# master_jorge2.net
KiCad netlist of a schematic drawn in EAGLE
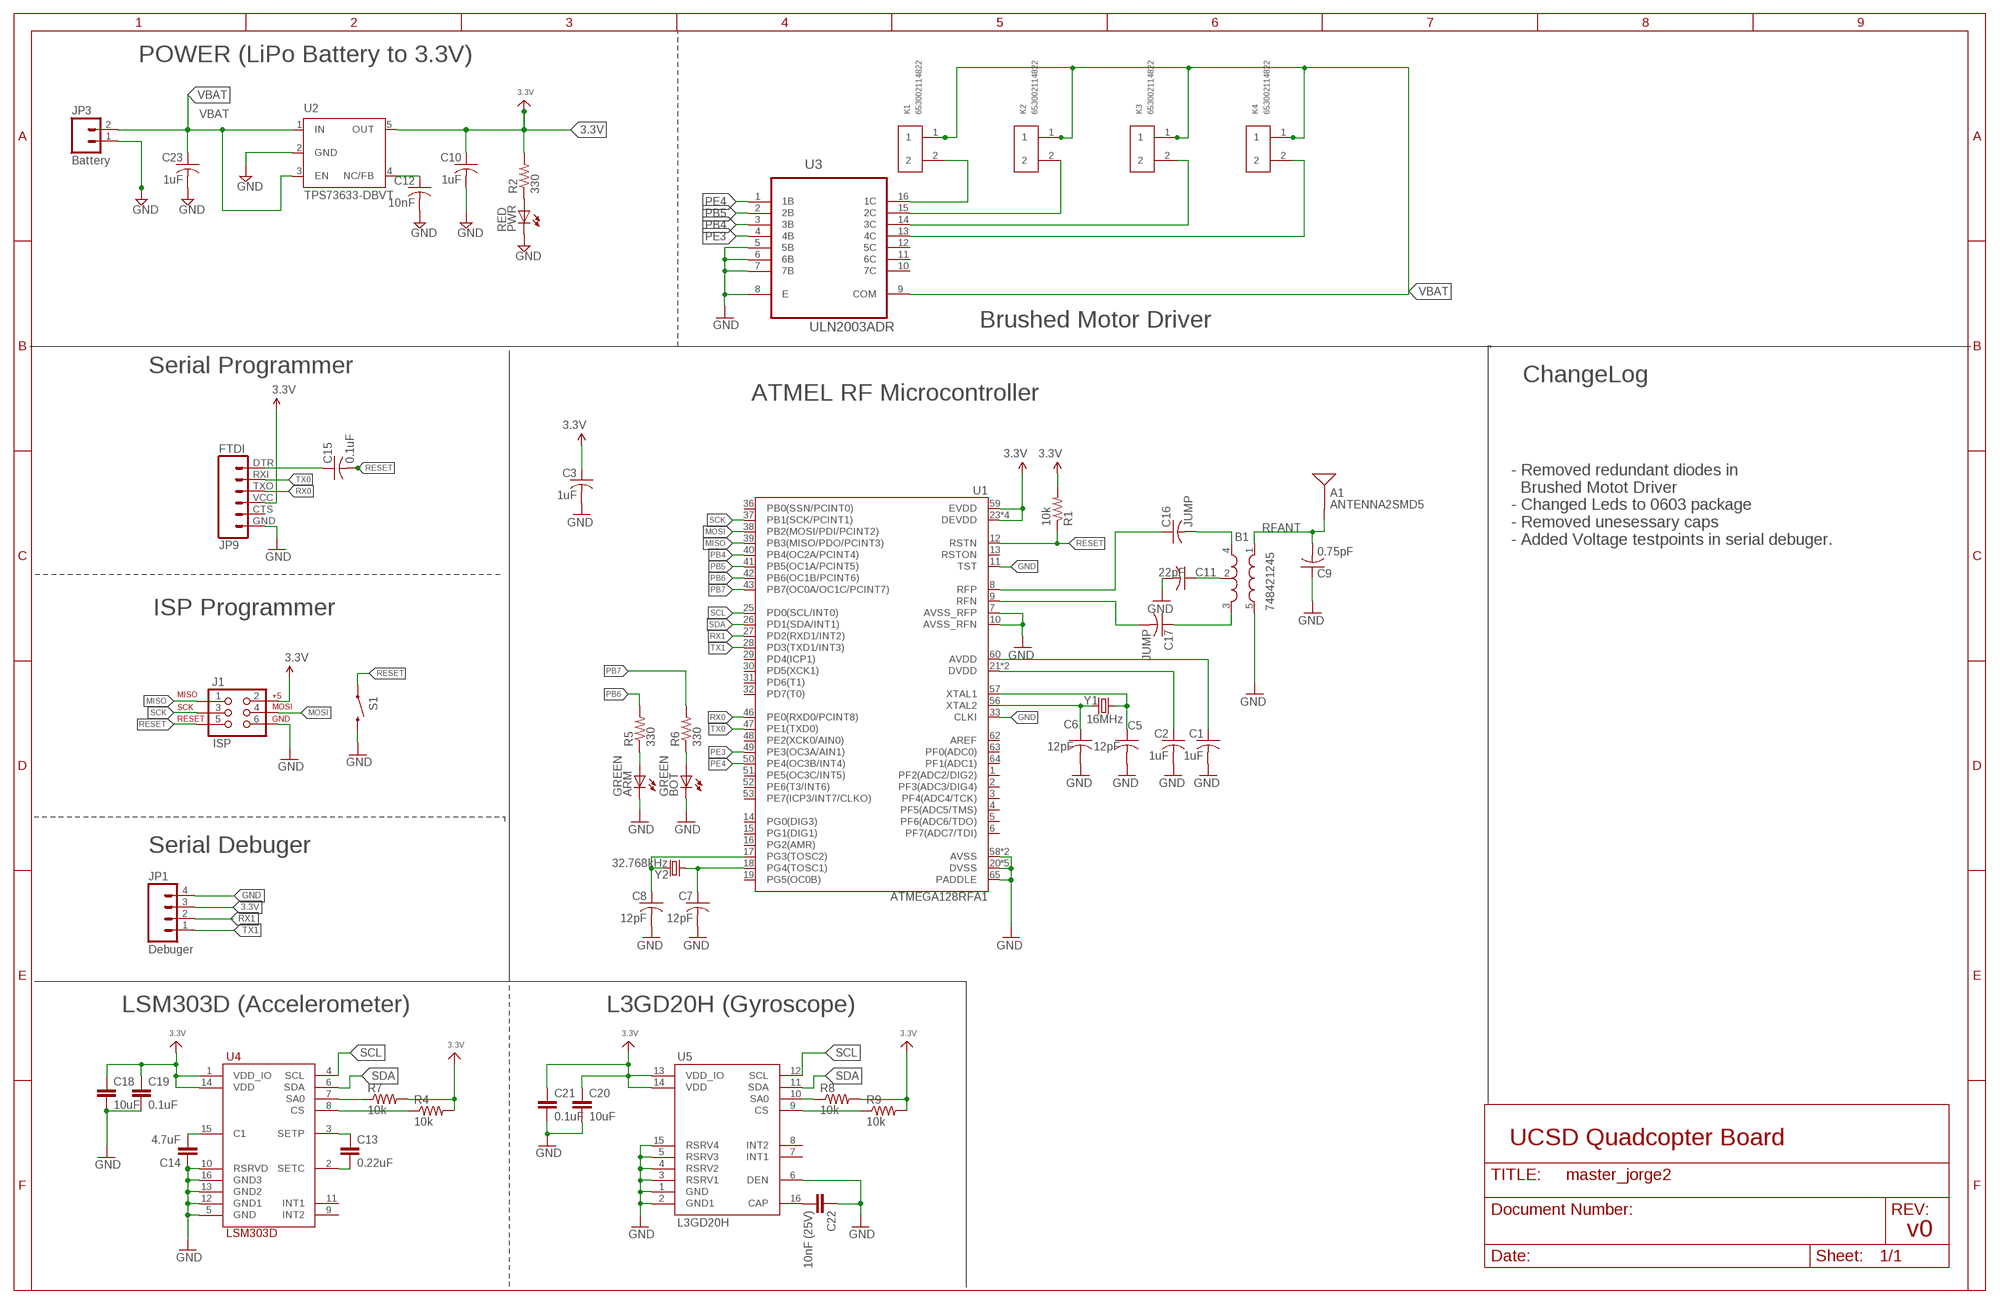
[diagram p0: schematic, sheet 1]

(export (version "E")
  (design (tool "Eeschema 10.0.6"))
  (components
    (comp (ref "A1")
      (value "ANTENNA2SMD5")
      (footprint "eagle-import:ANTENNA-CHIP5")
      (libsource (lib "eagle-import") (part "ANTENNA2SMD5"))
    )
    (comp (ref "ARM")
      (value "GREEN")
      (footprint "eagle-import:CHIPLED_0603")
      (libsource (lib "eagle-import") (part "LEDCHIPLED_0603"))
    )
    (comp (ref "B1")
      (value "748421245")
      (footprint "eagle-import:BALUN")
      (libsource (lib "eagle-import") (part "BALUN0805"))
    )
    (comp (ref "BOT")
      (value "GREEN")
      (footprint "eagle-import:CHIPLED_0603")
      (libsource (lib "eagle-import") (part "LEDCHIPLED_0603"))
    )
    (comp (ref "C1")
      (value "1uF")
      (footprint "eagle-import:C0805")
      (libsource (lib "eagle-import") (part "C-USC0805"))
    )
    (comp (ref "C2")
      (value "1uF")
      (footprint "eagle-import:C0805")
      (libsource (lib "eagle-import") (part "C-USC0805"))
    )
    (comp (ref "C3")
      (value "1uF")
      (footprint "eagle-import:C0805")
      (libsource (lib "eagle-import") (part "C-USC0805"))
    )
    (comp (ref "C5")
      (value "12pF")
      (footprint "eagle-import:C0805")
      (libsource (lib "eagle-import") (part "C-USC0805"))
    )
    (comp (ref "C6")
      (value "12pF")
      (footprint "eagle-import:C0805")
      (libsource (lib "eagle-import") (part "C-USC0805"))
    )
    (comp (ref "C7")
      (value "12pF")
      (footprint "eagle-import:C0805")
      (libsource (lib "eagle-import") (part "C-USC0805"))
    )
    (comp (ref "C8")
      (value "12pF")
      (footprint "eagle-import:C0805")
      (libsource (lib "eagle-import") (part "C-USC0805"))
    )
    (comp (ref "C9")
      (value "0.75pF")
      (footprint "eagle-import:C0805")
      (libsource (lib "eagle-import") (part "C-USC0805"))
    )
    (comp (ref "C10")
      (value "1uF")
      (footprint "eagle-import:C0805")
      (libsource (lib "eagle-import") (part "C-USC0805"))
    )
    (comp (ref "C11")
      (value "22pF")
      (footprint "eagle-import:C0805")
      (libsource (lib "eagle-import") (part "C-USC0805"))
    )
    (comp (ref "C12")
      (value "10nF")
      (footprint "eagle-import:C0805")
      (libsource (lib "eagle-import") (part "C-USC0805"))
    )
    (comp (ref "C13")
      (value "0.22uF")
      (footprint "eagle-import:0805")
      (libsource (lib "eagle-import") (part "CAP0805"))
    )
    (comp (ref "C14")
      (value "4.7uF")
      (footprint "eagle-import:0805")
      (libsource (lib "eagle-import") (part "CAP0805"))
    )
    (comp (ref "C15")
      (value "0.1uF")
      (footprint "eagle-import:C0805")
      (libsource (lib "eagle-import") (part "C-USC0805"))
    )
    (comp (ref "C16")
      (value "JUMP")
      (footprint "eagle-import:C0805")
      (libsource (lib "eagle-import") (part "C-USC0805"))
    )
    (comp (ref "C17")
      (value "JUMP")
      (footprint "eagle-import:C0805")
      (libsource (lib "eagle-import") (part "C-USC0805"))
    )
    (comp (ref "C18")
      (value "10uF")
      (footprint "eagle-import:0805")
      (libsource (lib "eagle-import") (part "CAP0805"))
    )
    (comp (ref "C19")
      (value "0.1uF")
      (footprint "eagle-import:0805")
      (libsource (lib "eagle-import") (part "CAP0805"))
    )
    (comp (ref "C20")
      (value "10uF")
      (footprint "eagle-import:0805")
      (libsource (lib "eagle-import") (part "CAP0805"))
    )
    (comp (ref "C21")
      (value "0.1uF")
      (footprint "eagle-import:0805")
      (libsource (lib "eagle-import") (part "CAP0805"))
    )
    (comp (ref "C22")
      (value "10nF (25V)")
      (footprint "eagle-import:0805")
      (libsource (lib "eagle-import") (part "CAP0805"))
    )
    (comp (ref "C23")
      (value "1uF")
      (footprint "eagle-import:C0805")
      (libsource (lib "eagle-import") (part "C-USC0805"))
    )
    (comp (ref "J1")
      (value "ISP")
      (footprint "eagle-import:2X3-NS")
      (libsource (lib "eagle-import") (part "AVR_SPI_PRG_6NS"))
    )
    (comp (ref "JP1")
      (value "Debuger")
      (footprint "eagle-import:1X04")
      (libsource (lib "eagle-import") (part "M04PTH"))
    )
    (comp (ref "JP3")
      (value "Battery")
      (footprint "eagle-import:1X02")
      (libsource (lib "eagle-import") (part "M02PTH"))
    )
    (comp (ref "JP9")
      (value "FTDI")
      (footprint "eagle-import:FTDI_BASIC")
      (libsource (lib "eagle-import") (part "FTDI_BASICPTH"))
    )
    (comp (ref "K1")
      (value "653002114822")
      (footprint "eagle-import:653002114822")
      (libsource (lib "eagle-import") (part "653002114822"))
    )
    (comp (ref "K2")
      (value "653002114822")
      (footprint "eagle-import:653002114822")
      (libsource (lib "eagle-import") (part "653002114822"))
    )
    (comp (ref "K3")
      (value "653002114822")
      (footprint "eagle-import:653002114822")
      (libsource (lib "eagle-import") (part "653002114822"))
    )
    (comp (ref "K4")
      (value "653002114822")
      (footprint "eagle-import:653002114822")
      (libsource (lib "eagle-import") (part "653002114822"))
    )
    (comp (ref "PWR")
      (value "RED")
      (footprint "eagle-import:CHIPLED_0603")
      (libsource (lib "eagle-import") (part "LEDCHIPLED_0603"))
    )
    (comp (ref "R1")
      (value "10k")
      (footprint "eagle-import:R0805")
      (libsource (lib "eagle-import") (part "R-US_R0805"))
    )
    (comp (ref "R2")
      (value "330")
      (footprint "eagle-import:R0805")
      (libsource (lib "eagle-import") (part "R-US_R0805"))
    )
    (comp (ref "R4")
      (value "10k")
      (footprint "eagle-import:0805")
      (libsource (lib "eagle-import") (part "RESISTOR0805-RES"))
    )
    (comp (ref "R5")
      (value "330")
      (footprint "eagle-import:R0805")
      (libsource (lib "eagle-import") (part "R-US_R0805"))
    )
    (comp (ref "R6")
      (value "330")
      (footprint "eagle-import:R0805")
      (libsource (lib "eagle-import") (part "R-US_R0805"))
    )
    (comp (ref "R7")
      (value "10k")
      (footprint "eagle-import:0805")
      (libsource (lib "eagle-import") (part "RESISTOR0805-RES"))
    )
    (comp (ref "R8")
      (value "10k")
      (footprint "eagle-import:0805")
      (libsource (lib "eagle-import") (part "RESISTOR0805-RES"))
    )
    (comp (ref "R9")
      (value "10k")
      (footprint "eagle-import:0805")
      (libsource (lib "eagle-import") (part "RESISTOR0805-RES"))
    )
    (comp (ref "S1")
      (value "SWITCH-MOMENTARY-2SMD")
      (footprint "eagle-import:TACTILE_SWITCH_SMD")
      (libsource (lib "eagle-import") (part "SWITCH-MOMENTARY-2SMD"))
    )
    (comp (ref "U1")
      (value "ATMEGA128RFA1")
      (footprint "eagle-import:QFN-64")
      (libsource (lib "eagle-import") (part "ATMEGA128RFA1"))
    )
    (comp (ref "U2")
      (value "TPS73633-DBVT")
      (footprint "eagle-import:SOT23-DBV")
      (libsource (lib "eagle-import") (part "TPS73633-DBVT"))
    )
    (comp (ref "U3")
      (value "ULN2003ADR")
      (footprint "eagle-import:SOIC127P600X175-16N")
      (libsource (lib "eagle-import") (part "ULN2003ADR"))
    )
    (comp (ref "U4")
      (value "LSM303D")
      (footprint "eagle-import:LGA16_3X3MM")
      (libsource (lib "eagle-import") (part "LSM303D"))
    )
    (comp (ref "U5")
      (value "L3GD20H")
      (footprint "eagle-import:LGA16_3X3MM")
      (libsource (lib "eagle-import") (part "L3GD20H"))
    )
    (comp (ref "Y1")
      (value "16MHz")
      (footprint "eagle-import:CRYSTAL-SMD-5X3")
      (libsource (lib "eagle-import") (part "CRYSTAL5X3"))
    )
    (comp (ref "Y2")
      (value "32.768kHz")
      (footprint "eagle-import:CRYSTAL-32KHZ-SMD")
      (libsource (lib "eagle-import") (part "CRYSTAL32-SMD"))
    )
  )
  (nets
    (net (code "1") (name "/RFANT") (class "Default")
      (node (ref "A1") (pin "FEED") (pinfunction "SIGNAL_FEED") (pintype "bidirectional"))
      (node (ref "B1") (pin "1") (pinfunction "IN_1") (pintype "bidirectional"))
      (node (ref "C9") (pin "2") (pinfunction "2_2") (pintype "passive"))
    )
    (net (code "2") (name "3.3V") (class "Default")
      (node (ref "C10") (pin "1") (pinfunction "1_1") (pintype "passive"))
      (node (ref "C18") (pin "1") (pinfunction "1_1") (pintype "passive"))
      (node (ref "C19") (pin "1") (pinfunction "1_1") (pintype "passive"))
      (node (ref "C20") (pin "1") (pinfunction "1_1") (pintype "passive"))
      (node (ref "C21") (pin "1") (pinfunction "1_1") (pintype "passive"))
      (node (ref "C3") (pin "1") (pinfunction "1_1") (pintype "passive"))
      (node (ref "J1") (pin "2") (pinfunction "2_2") (pintype "passive"))
      (node (ref "JP1") (pin "3") (pinfunction "3_3") (pintype "passive"))
      (node (ref "JP9") (pin "VCC") (pinfunction "4_VCC") (pintype "passive"))
      (node (ref "R1") (pin "2") (pinfunction "2_2") (pintype "passive"))
      (node (ref "R2") (pin "2") (pinfunction "2_2") (pintype "passive"))
      (node (ref "R4") (pin "2") (pinfunction "2_2") (pintype "passive"))
      (node (ref "R7") (pin "2") (pinfunction "2_2") (pintype "passive"))
      (node (ref "R8") (pin "2") (pinfunction "2_2") (pintype "passive"))
      (node (ref "R9") (pin "2") (pinfunction "2_2") (pintype "passive"))
      (node (ref "U1") (pin "23") (pinfunction "DEVDD_23") (pintype "bidirectional"))
      (node (ref "U1") (pin "34") (pinfunction "DEVDD_34") (pintype "bidirectional"))
      (node (ref "U1") (pin "44") (pinfunction "DEVDD_44") (pintype "bidirectional"))
      (node (ref "U1") (pin "54") (pinfunction "DEVDD_54") (pintype "bidirectional"))
      (node (ref "U1") (pin "59") (pinfunction "EVDD_59") (pintype "bidirectional"))
      (node (ref "U2") (pin "5") (pinfunction "OUT_5") (pintype "passive"))
      (node (ref "U4") (pin "1") (pinfunction "VDD_IO_1") (pintype "bidirectional"))
      (node (ref "U4") (pin "14") (pinfunction "VDD_14") (pintype "bidirectional"))
      (node (ref "U5") (pin "13") (pinfunction "VDD_IO_13") (pintype "bidirectional"))
      (node (ref "U5") (pin "14") (pinfunction "VDD_14") (pintype "bidirectional"))
    )
    (net (code "3") (name "GND") (class "Default")
      (node (ref "ARM") (pin "C") (pinfunction "C_C") (pintype "passive"))
      (node (ref "B1") (pin "5") (pinfunction "GND_5") (pintype "bidirectional"))
      (node (ref "BOT") (pin "C") (pinfunction "C_C") (pintype "passive"))
      (node (ref "C1") (pin "2") (pinfunction "2_2") (pintype "passive"))
      (node (ref "C10") (pin "2") (pinfunction "2_2") (pintype "passive"))
      (node (ref "C11") (pin "2") (pinfunction "2_2") (pintype "passive"))
      (node (ref "C12") (pin "2") (pinfunction "2_2") (pintype "passive"))
      (node (ref "C14") (pin "1") (pinfunction "1_1") (pintype "passive"))
      (node (ref "C18") (pin "2") (pinfunction "2_2") (pintype "passive"))
      (node (ref "C19") (pin "2") (pinfunction "2_2") (pintype "passive"))
      (node (ref "C2") (pin "2") (pinfunction "2_2") (pintype "passive"))
      (node (ref "C20") (pin "2") (pinfunction "2_2") (pintype "passive"))
      (node (ref "C21") (pin "2") (pinfunction "2_2") (pintype "passive"))
      (node (ref "C22") (pin "1") (pinfunction "1_1") (pintype "passive"))
      (node (ref "C23") (pin "2") (pinfunction "2_2") (pintype "passive"))
      (node (ref "C3") (pin "2") (pinfunction "2_2") (pintype "passive"))
      (node (ref "C5") (pin "2") (pinfunction "2_2") (pintype "passive"))
      (node (ref "C6") (pin "2") (pinfunction "2_2") (pintype "passive"))
      (node (ref "C7") (pin "2") (pinfunction "2_2") (pintype "passive"))
      (node (ref "C8") (pin "2") (pinfunction "2_2") (pintype "passive"))
      (node (ref "C9") (pin "1") (pinfunction "1_1") (pintype "passive"))
      (node (ref "J1") (pin "6") (pinfunction "6_6") (pintype "passive"))
      (node (ref "JP1") (pin "4") (pinfunction "4_4") (pintype "passive"))
      (node (ref "JP3") (pin "1") (pinfunction "1_1") (pintype "passive"))
      (node (ref "JP9") (pin "GND") (pinfunction "6_GND") (pintype "passive"))
      (node (ref "PWR") (pin "C") (pinfunction "C_C") (pintype "passive"))
      (node (ref "S1") (pin "3") (pinfunction "2_3") (pintype "passive"))
      (node (ref "U1") (pin "10") (pinfunction "AVSS_RFN_10") (pintype "bidirectional"))
      (node (ref "U1") (pin "11") (pinfunction "TST_11") (pintype "bidirectional"))
      (node (ref "U1") (pin "20") (pinfunction "DVSS_20") (pintype "bidirectional"))
      (node (ref "U1") (pin "24") (pinfunction "DVSS_24") (pintype "bidirectional"))
      (node (ref "U1") (pin "33") (pinfunction "CLKI_33") (pintype "bidirectional"))
      (node (ref "U1") (pin "35") (pinfunction "DVSS_35") (pintype "bidirectional"))
      (node (ref "U1") (pin "45") (pinfunction "DVSS_45") (pintype "bidirectional"))
      (node (ref "U1") (pin "55") (pinfunction "DVSS_55") (pintype "bidirectional"))
      (node (ref "U1") (pin "58") (pinfunction "AVSS_58") (pintype "bidirectional"))
      (node (ref "U1") (pin "61") (pinfunction "AVSS_61") (pintype "bidirectional"))
      (node (ref "U1") (pin "65") (pinfunction "PADDLE_65") (pintype "bidirectional"))
      (node (ref "U1") (pin "7") (pinfunction "AVSS_RFP_7") (pintype "bidirectional"))
      (node (ref "U2") (pin "2") (pinfunction "GND_2") (pintype "input"))
      (node (ref "U3") (pin "5") (pinfunction "5B_5") (pintype "input"))
      (node (ref "U3") (pin "6") (pinfunction "6B_6") (pintype "input"))
      (node (ref "U3") (pin "7") (pinfunction "7B_7") (pintype "input"))
      (node (ref "U3") (pin "8") (pinfunction "E_8") (pintype "input"))
      (node (ref "U4") (pin "10") (pinfunction "RSRVD_10") (pintype "bidirectional"))
      (node (ref "U4") (pin "12") (pinfunction "GND1_12") (pintype "bidirectional"))
      (node (ref "U4") (pin "13") (pinfunction "GND2_13") (pintype "bidirectional"))
      (node (ref "U4") (pin "16") (pinfunction "GND3_16") (pintype "bidirectional"))
      (node (ref "U4") (pin "5") (pinfunction "GND_5") (pintype "bidirectional"))
      (node (ref "U5") (pin "1") (pinfunction "GND_1") (pintype "bidirectional"))
      (node (ref "U5") (pin "15") (pinfunction "RSRV4_15") (pintype "bidirectional"))
      (node (ref "U5") (pin "2") (pinfunction "GND1_2") (pintype "bidirectional"))
      (node (ref "U5") (pin "3") (pinfunction "RSRV1_3") (pintype "bidirectional"))
      (node (ref "U5") (pin "4") (pinfunction "RSRV2_4") (pintype "bidirectional"))
      (node (ref "U5") (pin "5") (pinfunction "RSRV3_5") (pintype "bidirectional"))
      (node (ref "U5") (pin "6") (pinfunction "DEN_6") (pintype "bidirectional"))
    )
    (net (code "4") (name "MISO") (class "Default")
      (node (ref "J1") (pin "1") (pinfunction "1_1") (pintype "passive"))
      (node (ref "U1") (pin "39") (pinfunction "PB3(MISO/PDO/PCINT3)_39") (pintype "bidirectional"))
    )
    (net (code "5") (name "MOSI") (class "Default")
      (node (ref "J1") (pin "4") (pinfunction "4_4") (pintype "passive"))
      (node (ref "U1") (pin "38") (pinfunction "PB2(MOSI/PDI/PCINT2)_38") (pintype "bidirectional"))
    )
    (net (code "6") (name "Net-(ARM-PadA)") (class "Default")
      (node (ref "ARM") (pin "A") (pinfunction "A_A") (pintype "passive"))
      (node (ref "R5") (pin "1") (pinfunction "1_1") (pintype "passive"))
    )
    (net (code "7") (name "Net-(B1-GND-Pad2)") (class "Default")
      (node (ref "B1") (pin "2") (pinfunction "GND_2") (pintype "bidirectional"))
      (node (ref "C11") (pin "1") (pinfunction "1_1") (pintype "passive"))
    )
    (net (code "8") (name "Net-(B1-OUT1)") (class "Default")
      (node (ref "B1") (pin "4") (pinfunction "OUT1_4") (pintype "bidirectional"))
      (node (ref "C16") (pin "2") (pinfunction "2_2") (pintype "passive"))
    )
    (net (code "9") (name "Net-(B1-OUT2)") (class "Default")
      (node (ref "B1") (pin "3") (pinfunction "OUT2_3") (pintype "bidirectional"))
      (node (ref "C17") (pin "1") (pinfunction "1_1") (pintype "passive"))
    )
    (net (code "10") (name "Net-(BOT-PadA)") (class "Default")
      (node (ref "BOT") (pin "A") (pinfunction "A_A") (pintype "passive"))
      (node (ref "R6") (pin "1") (pinfunction "1_1") (pintype "passive"))
    )
    (net (code "11") (name "Net-(C2-Pad1)") (class "Default")
      (node (ref "C2") (pin "1") (pinfunction "1_1") (pintype "passive"))
      (node (ref "U1") (pin "21") (pinfunction "DVDD_21") (pintype "bidirectional"))
      (node (ref "U1") (pin "22") (pinfunction "DVDD_22") (pintype "bidirectional"))
    )
    (net (code "12") (name "Net-(JP9-1)") (class "Default")
      (node (ref "C15") (pin "1") (pinfunction "1_1") (pintype "passive"))
      (node (ref "JP9") (pin "DTR") (pinfunction "1_DTR") (pintype "passive"))
    )
    (net (code "13") (name "Net-(PWR-PadA)") (class "Default")
      (node (ref "PWR") (pin "A") (pinfunction "A_A") (pintype "passive"))
      (node (ref "R2") (pin "1") (pinfunction "1_1") (pintype "passive"))
    )
    (net (code "14") (name "Net-(U1-AVDD)") (class "Default")
      (node (ref "C1") (pin "1") (pinfunction "1_1") (pintype "passive"))
      (node (ref "U1") (pin "60") (pinfunction "AVDD_60") (pintype "bidirectional"))
    )
    (net (code "15") (name "Net-(U1-PG3(TOSC2))") (class "Default")
      (node (ref "C8") (pin "1") (pinfunction "1_1") (pintype "passive"))
      (node (ref "U1") (pin "17") (pinfunction "PG3(TOSC2)_17") (pintype "bidirectional"))
      (node (ref "Y2") (pin "X2") (pinfunction "2_X2") (pintype "passive"))
    )
    (net (code "16") (name "Net-(U1-PG4(TOSC1))") (class "Default")
      (node (ref "C7") (pin "1") (pinfunction "1_1") (pintype "passive"))
      (node (ref "U1") (pin "18") (pinfunction "PG4(TOSC1)_18") (pintype "bidirectional"))
      (node (ref "Y2") (pin "X1") (pinfunction "1_X1") (pintype "passive"))
    )
    (net (code "17") (name "Net-(U1-RFN)") (class "Default")
      (node (ref "C17") (pin "2") (pinfunction "2_2") (pintype "passive"))
      (node (ref "U1") (pin "9") (pinfunction "RFN_9") (pintype "bidirectional"))
    )
    (net (code "18") (name "Net-(U1-RFP)") (class "Default")
      (node (ref "C16") (pin "1") (pinfunction "1_1") (pintype "passive"))
      (node (ref "U1") (pin "8") (pinfunction "RFP_8") (pintype "bidirectional"))
    )
    (net (code "19") (name "Net-(U1-XTAL1)") (class "Default")
      (node (ref "C5") (pin "1") (pinfunction "1_1") (pintype "passive"))
      (node (ref "U1") (pin "57") (pinfunction "XTAL1_57") (pintype "bidirectional"))
      (node (ref "Y1") (pin "3") (pinfunction "2_3") (pintype "passive"))
    )
    (net (code "20") (name "Net-(U1-XTAL2)") (class "Default")
      (node (ref "C6") (pin "1") (pinfunction "1_1") (pintype "passive"))
      (node (ref "U1") (pin "56") (pinfunction "XTAL2_56") (pintype "bidirectional"))
      (node (ref "Y1") (pin "1") (pinfunction "1_1") (pintype "passive"))
    )
    (net (code "21") (name "Net-(U2-NC{slash}FB)") (class "Default")
      (node (ref "C12") (pin "1") (pinfunction "1_1") (pintype "passive"))
      (node (ref "U2") (pin "4") (pinfunction "NC/FB_4") (pintype "passive"))
    )
    (net (code "22") (name "Net-(U3-1C)") (class "Default")
      (node (ref "K1") (pin "2") (pinfunction "2_2") (pintype "bidirectional"))
      (node (ref "U3") (pin "16") (pinfunction "1C_16") (pintype "output"))
    )
    (net (code "23") (name "Net-(U3-2C)") (class "Default")
      (node (ref "K2") (pin "2") (pinfunction "2_2") (pintype "bidirectional"))
      (node (ref "U3") (pin "15") (pinfunction "2C_15") (pintype "output"))
    )
    (net (code "24") (name "Net-(U3-3C)") (class "Default")
      (node (ref "K3") (pin "2") (pinfunction "2_2") (pintype "bidirectional"))
      (node (ref "U3") (pin "14") (pinfunction "3C_14") (pintype "output"))
    )
    (net (code "25") (name "Net-(U3-4C)") (class "Default")
      (node (ref "K4") (pin "2") (pinfunction "2_2") (pintype "bidirectional"))
      (node (ref "U3") (pin "13") (pinfunction "4C_13") (pintype "output"))
    )
    (net (code "26") (name "Net-(U4-C1)") (class "Default")
      (node (ref "C14") (pin "2") (pinfunction "2_2") (pintype "passive"))
      (node (ref "U4") (pin "15") (pinfunction "C1_15") (pintype "bidirectional"))
    )
    (net (code "27") (name "Net-(U4-CS)") (class "Default")
      (node (ref "R4") (pin "1") (pinfunction "1_1") (pintype "passive"))
      (node (ref "U4") (pin "8") (pinfunction "CS_8") (pintype "bidirectional"))
    )
    (net (code "28") (name "Net-(U4-SA0)") (class "Default")
      (node (ref "R7") (pin "1") (pinfunction "1_1") (pintype "passive"))
      (node (ref "U4") (pin "7") (pinfunction "SA0_7") (pintype "bidirectional"))
    )
    (net (code "29") (name "Net-(U4-SETC)") (class "Default")
      (node (ref "C13") (pin "2") (pinfunction "2_2") (pintype "passive"))
      (node (ref "U4") (pin "2") (pinfunction "SETC_2") (pintype "bidirectional"))
    )
    (net (code "30") (name "Net-(U4-SETP)") (class "Default")
      (node (ref "C13") (pin "1") (pinfunction "1_1") (pintype "passive"))
      (node (ref "U4") (pin "3") (pinfunction "SETP_3") (pintype "bidirectional"))
    )
    (net (code "31") (name "Net-(U5-CAP)") (class "Default")
      (node (ref "C22") (pin "2") (pinfunction "2_2") (pintype "passive"))
      (node (ref "U5") (pin "16") (pinfunction "CAP_16") (pintype "bidirectional"))
    )
    (net (code "32") (name "Net-(U5-CS)") (class "Default")
      (node (ref "R9") (pin "1") (pinfunction "1_1") (pintype "passive"))
      (node (ref "U5") (pin "9") (pinfunction "CS_9") (pintype "bidirectional"))
    )
    (net (code "33") (name "Net-(U5-SA0)") (class "Default")
      (node (ref "R8") (pin "1") (pinfunction "1_1") (pintype "passive"))
      (node (ref "U5") (pin "10") (pinfunction "SA0_10") (pintype "bidirectional"))
    )
    (net (code "34") (name "PB4") (class "Default")
      (node (ref "U1") (pin "40") (pinfunction "PB4(OC2A/PCINT4)_40") (pintype "bidirectional"))
      (node (ref "U3") (pin "3") (pinfunction "3B_3") (pintype "input"))
    )
    (net (code "35") (name "PB5") (class "Default")
      (node (ref "U1") (pin "41") (pinfunction "PB5(OC1A/PCINT5)_41") (pintype "bidirectional"))
      (node (ref "U3") (pin "2") (pinfunction "2B_2") (pintype "input"))
    )
    (net (code "36") (name "PB6") (class "Default")
      (node (ref "R5") (pin "2") (pinfunction "2_2") (pintype "passive"))
      (node (ref "U1") (pin "42") (pinfunction "PB6(OC1B/PCINT6)_42") (pintype "bidirectional"))
    )
    (net (code "37") (name "PB7") (class "Default")
      (node (ref "R6") (pin "2") (pinfunction "2_2") (pintype "passive"))
      (node (ref "U1") (pin "43") (pinfunction "PB7(OC0A/OC1C/PCINT7)_43") (pintype "bidirectional"))
    )
    (net (code "38") (name "PE3") (class "Default")
      (node (ref "U1") (pin "49") (pinfunction "PE3(OC3A/AIN1)_49") (pintype "bidirectional"))
      (node (ref "U3") (pin "4") (pinfunction "4B_4") (pintype "input"))
    )
    (net (code "39") (name "PE4") (class "Default")
      (node (ref "U1") (pin "50") (pinfunction "PE4(OC3B/INT4)_50") (pintype "bidirectional"))
      (node (ref "U3") (pin "1") (pinfunction "1B_1") (pintype "input"))
    )
    (net (code "40") (name "RESET") (class "Default")
      (node (ref "C15") (pin "2") (pinfunction "2_2") (pintype "passive"))
      (node (ref "J1") (pin "5") (pinfunction "5_5") (pintype "passive"))
      (node (ref "R1") (pin "1") (pinfunction "1_1") (pintype "passive"))
      (node (ref "S1") (pin "1") (pinfunction "1_1") (pintype "passive"))
      (node (ref "U1") (pin "12") (pinfunction "RSTN_12") (pintype "bidirectional"))
    )
    (net (code "41") (name "RX0") (class "Default")
      (node (ref "JP9") (pin "TXO") (pinfunction "3_TXO") (pintype "passive"))
      (node (ref "U1") (pin "46") (pinfunction "PE0(RXD0/PCINT8)_46") (pintype "bidirectional"))
    )
    (net (code "42") (name "RX1") (class "Default")
      (node (ref "JP1") (pin "2") (pinfunction "2_2") (pintype "passive"))
      (node (ref "U1") (pin "27") (pinfunction "PD2(RXD1/INT2)_27") (pintype "bidirectional"))
    )
    (net (code "43") (name "SCK") (class "Default")
      (node (ref "J1") (pin "3") (pinfunction "3_3") (pintype "passive"))
      (node (ref "U1") (pin "37") (pinfunction "PB1(SCK/PCINT1)_37") (pintype "bidirectional"))
    )
    (net (code "44") (name "SCL") (class "Default")
      (node (ref "U1") (pin "25") (pinfunction "PD0(SCL/INT0)_25") (pintype "bidirectional"))
      (node (ref "U4") (pin "4") (pinfunction "SCL_4") (pintype "bidirectional"))
      (node (ref "U5") (pin "12") (pinfunction "SCL_12") (pintype "bidirectional"))
    )
    (net (code "45") (name "SDA") (class "Default")
      (node (ref "U1") (pin "26") (pinfunction "PD1(SDA/INT1)_26") (pintype "bidirectional"))
      (node (ref "U4") (pin "6") (pinfunction "SDA_6") (pintype "bidirectional"))
      (node (ref "U5") (pin "11") (pinfunction "SDA_11") (pintype "bidirectional"))
    )
    (net (code "46") (name "TX0") (class "Default")
      (node (ref "JP9") (pin "RXI") (pinfunction "2_RXI") (pintype "passive"))
      (node (ref "U1") (pin "47") (pinfunction "PE1(TXD0)_47") (pintype "bidirectional"))
    )
    (net (code "47") (name "TX1") (class "Default")
      (node (ref "JP1") (pin "1") (pinfunction "1_1") (pintype "passive"))
      (node (ref "U1") (pin "28") (pinfunction "PD3(TXD1/INT3)_28") (pintype "bidirectional"))
    )
    (net (code "48") (name "VBAT") (class "Default")
      (node (ref "C23") (pin "1") (pinfunction "1_1") (pintype "passive"))
      (node (ref "JP3") (pin "2") (pinfunction "2_2") (pintype "passive"))
      (node (ref "K1") (pin "1") (pinfunction "1_1") (pintype "bidirectional"))
      (node (ref "K2") (pin "1") (pinfunction "1_1") (pintype "bidirectional"))
      (node (ref "K3") (pin "1") (pinfunction "1_1") (pintype "bidirectional"))
      (node (ref "K4") (pin "1") (pinfunction "1_1") (pintype "bidirectional"))
      (node (ref "U2") (pin "1") (pinfunction "IN_1") (pintype "input"))
      (node (ref "U2") (pin "3") (pinfunction "EN_3") (pintype "power_in"))
      (node (ref "U3") (pin "9") (pinfunction "COM_9") (pintype "output"))
    )
    (net (code "49") (name "unconnected-(JP9-5-PadCTS)") (class "Default")
      (node (ref "JP9") (pin "CTS") (pinfunction "5_CTS") (pintype "passive"))
    )
    (net (code "50") (name "unconnected-(U1-AREF-Pad62)") (class "Default")
      (node (ref "U1") (pin "62") (pinfunction "AREF_62") (pintype "bidirectional"))
    )
    (net (code "51") (name "unconnected-(U1-PB0(SSN{slash}PCINT0)-Pad36)") (class "Default")
      (node (ref "U1") (pin "36") (pinfunction "PB0(SSN/PCINT0)_36") (pintype "bidirectional"))
    )
    (net (code "52") (name "unconnected-(U1-PD4(ICP1)-Pad29)") (class "Default")
      (node (ref "U1") (pin "29") (pinfunction "PD4(ICP1)_29") (pintype "bidirectional"))
    )
    (net (code "53") (name "unconnected-(U1-PD5(XCK1)-Pad30)") (class "Default")
      (node (ref "U1") (pin "30") (pinfunction "PD5(XCK1)_30") (pintype "bidirectional"))
    )
    (net (code "54") (name "unconnected-(U1-PD6(T1)-Pad31)") (class "Default")
      (node (ref "U1") (pin "31") (pinfunction "PD6(T1)_31") (pintype "bidirectional"))
    )
    (net (code "55") (name "unconnected-(U1-PD7(T0)-Pad32)") (class "Default")
      (node (ref "U1") (pin "32") (pinfunction "PD7(T0)_32") (pintype "bidirectional"))
    )
    (net (code "56") (name "unconnected-(U1-PE2(XCK0{slash}AIN0)-Pad48)") (class "Default")
      (node (ref "U1") (pin "48") (pinfunction "PE2(XCK0/AIN0)_48") (pintype "bidirectional"))
    )
    (net (code "57") (name "unconnected-(U1-PE5(OC3C{slash}INT5)-Pad51)") (class "Default")
      (node (ref "U1") (pin "51") (pinfunction "PE5(OC3C/INT5)_51") (pintype "bidirectional"))
    )
    (net (code "58") (name "unconnected-(U1-PE6(T3{slash}INT6)-Pad52)") (class "Default")
      (node (ref "U1") (pin "52") (pinfunction "PE6(T3/INT6)_52") (pintype "bidirectional"))
    )
    (net (code "59") (name "unconnected-(U1-PE7(ICP3{slash}INT7{slash}CLKO)-Pad53)") (class "Default")
      (node (ref "U1") (pin "53") (pinfunction "PE7(ICP3/INT7/CLKO)_53") (pintype "bidirectional"))
    )
    (net (code "60") (name "unconnected-(U1-PF0(ADC0)-Pad63)") (class "Default")
      (node (ref "U1") (pin "63") (pinfunction "PF0(ADC0)_63") (pintype "bidirectional"))
    )
    (net (code "61") (name "unconnected-(U1-PF1(ADC1)-Pad64)") (class "Default")
      (node (ref "U1") (pin "64") (pinfunction "PF1(ADC1)_64") (pintype "bidirectional"))
    )
    (net (code "62") (name "unconnected-(U1-PF2(ADC2{slash}DIG2)-Pad1)") (class "Default")
      (node (ref "U1") (pin "1") (pinfunction "PF2(ADC2/DIG2)_1") (pintype "bidirectional"))
    )
    (net (code "63") (name "unconnected-(U1-PF3(ADC3{slash}DIG4)-Pad2)") (class "Default")
      (node (ref "U1") (pin "2") (pinfunction "PF3(ADC3/DIG4)_2") (pintype "bidirectional"))
    )
    (net (code "64") (name "unconnected-(U1-PF4(ADC4{slash}TCK)-Pad3)") (class "Default")
      (node (ref "U1") (pin "3") (pinfunction "PF4(ADC4/TCK)_3") (pintype "bidirectional"))
    )
    (net (code "65") (name "unconnected-(U1-PF5(ADC5{slash}TMS)-Pad4)") (class "Default")
      (node (ref "U1") (pin "4") (pinfunction "PF5(ADC5/TMS)_4") (pintype "bidirectional"))
    )
    (net (code "66") (name "unconnected-(U1-PF6(ADC6{slash}TDO)-Pad5)") (class "Default")
      (node (ref "U1") (pin "5") (pinfunction "PF6(ADC6/TDO)_5") (pintype "bidirectional"))
    )
    (net (code "67") (name "unconnected-(U1-PF7(ADC7{slash}TDI)-Pad6)") (class "Default")
      (node (ref "U1") (pin "6") (pinfunction "PF7(ADC7/TDI)_6") (pintype "bidirectional"))
    )
    (net (code "68") (name "unconnected-(U1-PG0(DIG3)-Pad14)") (class "Default")
      (node (ref "U1") (pin "14") (pinfunction "PG0(DIG3)_14") (pintype "bidirectional"))
    )
    (net (code "69") (name "unconnected-(U1-PG1(DIG1)-Pad15)") (class "Default")
      (node (ref "U1") (pin "15") (pinfunction "PG1(DIG1)_15") (pintype "bidirectional"))
    )
    (net (code "70") (name "unconnected-(U1-PG2(AMR)-Pad16)") (class "Default")
      (node (ref "U1") (pin "16") (pinfunction "PG2(AMR)_16") (pintype "bidirectional"))
    )
    (net (code "71") (name "unconnected-(U1-PG5(OC0B)-Pad19)") (class "Default")
      (node (ref "U1") (pin "19") (pinfunction "PG5(OC0B)_19") (pintype "bidirectional"))
    )
    (net (code "72") (name "unconnected-(U1-RSTON-Pad13)") (class "Default")
      (node (ref "U1") (pin "13") (pinfunction "RSTON_13") (pintype "bidirectional"))
    )
    (net (code "73") (name "unconnected-(U3-5C-Pad12)") (class "Default")
      (node (ref "U3") (pin "12") (pinfunction "5C_12") (pintype "output"))
    )
    (net (code "74") (name "unconnected-(U3-6C-Pad11)") (class "Default")
      (node (ref "U3") (pin "11") (pinfunction "6C_11") (pintype "output"))
    )
    (net (code "75") (name "unconnected-(U3-7C-Pad10)") (class "Default")
      (node (ref "U3") (pin "10") (pinfunction "7C_10") (pintype "output"))
    )
    (net (code "76") (name "unconnected-(U4-INT1-Pad11)") (class "Default")
      (node (ref "U4") (pin "11") (pinfunction "INT1_11") (pintype "bidirectional"))
    )
    (net (code "77") (name "unconnected-(U4-INT2-Pad9)") (class "Default")
      (node (ref "U4") (pin "9") (pinfunction "INT2_9") (pintype "bidirectional"))
    )
    (net (code "78") (name "unconnected-(U5-INT1-Pad7)") (class "Default")
      (node (ref "U5") (pin "7") (pinfunction "INT1_7") (pintype "bidirectional"))
    )
    (net (code "79") (name "unconnected-(U5-INT2-Pad8)") (class "Default")
      (node (ref "U5") (pin "8") (pinfunction "INT2_8") (pintype "bidirectional"))
    )
  )
)
